# 2_power.net
KiCad netlist of a schematic drawn in Altium Designer
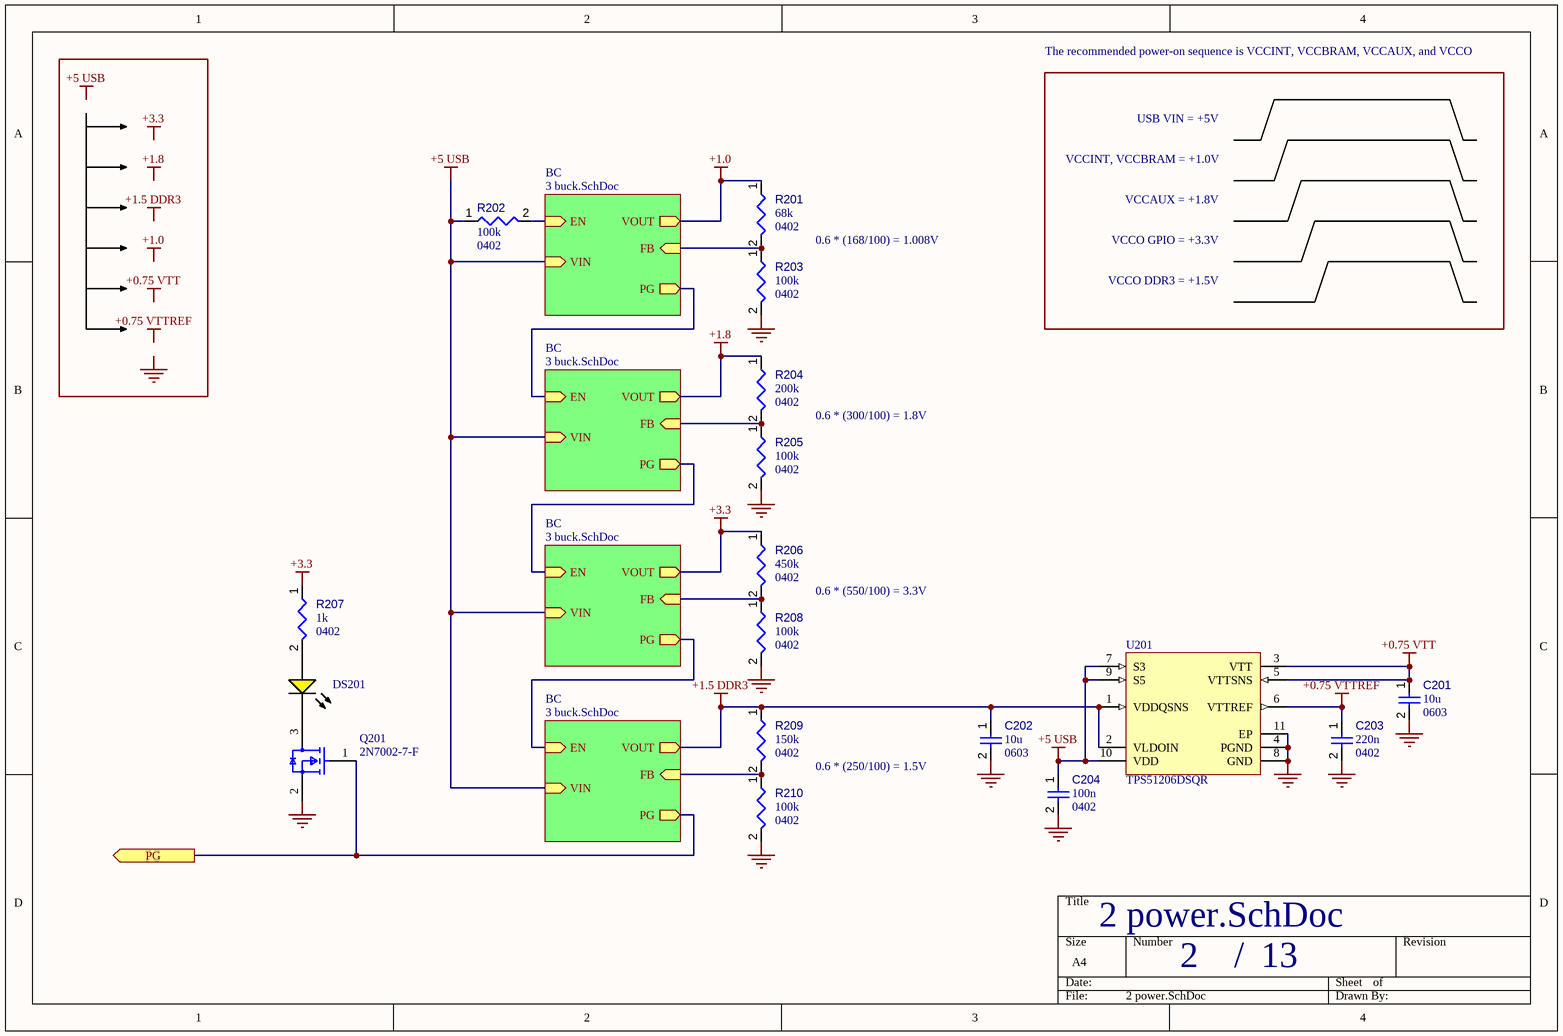
[diagram p0: 2 power.SchDoc]

(export (version "E")
  (design (tool "Eeschema 10.0.6"))
  (components
    (comp (ref "C201")
      (value "10u")
      (footprint "CAPC0603(1608)100_L")
      (description "Capacitor")
      (fields (field (name "CASE/PACKAGE") "0603") (field (name "Comment") "Capacitors,0603,10u"))
      (libsource (lib "UBC Uncrewed Aircraft Systems") (part "CAP-NP-2"))
    )
    (comp (ref "C202")
      (value "10u")
      (footprint "CAPC0603(1608)100_L")
      (description "Capacitor")
      (fields (field (name "CASE/PACKAGE") "0603") (field (name "Comment") "Capacitors,0603,10u"))
      (libsource (lib "UBC Uncrewed Aircraft Systems") (part "CAP-NP-2"))
    )
    (comp (ref "C203")
      (value "220n")
      (footprint "CAPC0402(1005)60_L")
      (description "Capacitor")
      (fields (field (name "CASE/PACKAGE") "0402") (field (name "Comment") "Capacitors,0402,220n,16"))
      (libsource (lib "UBC Uncrewed Aircraft Systems") (part "CAP-NP-2"))
    )
    (comp (ref "C204")
      (value "100n")
      (footprint "CAPC0402(1005)60_L")
      (description "Capacitor")
      (fields (field (name "CASE/PACKAGE") "0402") (field (name "Comment") "Capacitors,0402,100n,16"))
      (libsource (lib "UBC Uncrewed Aircraft Systems") (part "CAP-NP-2"))
    )
    (comp (ref "DS201")
      (value "SML-LX0603YW-TR")
      (footprint "LUMX-SML-LX0603_V")
      (fields (field (name "MANUFACTURER") "Lumex"))
      (libsource (lib "Altium Content Vault") (part "LED-YELLOW-AK-2"))
    )
    (comp (ref "Q201")
      (value "2N7002-7-F")
      (footprint "FP-SOT23-MFG")
      (description "MOSFET N-CH 60V 115MA SOT23-3")
      (fields (field (name "VOLTAGE") "60V"))
      (libsource (lib "Altium Content Vault") (part "3b9c635fedb024a5347a57b145af9cc"))
    )
    (comp (ref "R201")
      (value "68k")
      (footprint "RESC0402(1005)_L")
      (description "Resistor")
      (fields
        (field (name "CASE/PACKAGE") "0402")
        (field (name "TOLERANCE") "1%")
        (field (name "Comment") "Resistors,0402,1%,68k")
      )
      (libsource (lib "UBC Uncrewed Aircraft Systems") (part "RES-2"))
    )
    (comp (ref "R202")
      (value "100k")
      (footprint "RESC0402(1005)_L")
      (description "Resistor")
      (fields
        (field (name "CASE/PACKAGE") "0402")
        (field (name "TOLERANCE") "1%")
        (field (name "Comment") "Resistors,0402,1%,100k")
      )
      (libsource (lib "UBC Uncrewed Aircraft Systems") (part "RES-2"))
    )
    (comp (ref "R203")
      (value "100k")
      (footprint "RESC0402(1005)_L")
      (description "Resistor")
      (fields
        (field (name "CASE/PACKAGE") "0402")
        (field (name "TOLERANCE") "1%")
        (field (name "Comment") "Resistors,0402,1%,100k")
      )
      (libsource (lib "UBC Uncrewed Aircraft Systems") (part "RES-2"))
    )
    (comp (ref "R204")
      (value "200k")
      (footprint "RESC0402(1005)_L")
      (description "Resistor")
      (fields
        (field (name "CASE/PACKAGE") "0402")
        (field (name "TOLERANCE") "1%")
        (field (name "Comment") "Resistors,0402,1%,200k")
      )
      (libsource (lib "UBC Uncrewed Aircraft Systems") (part "RES-2"))
    )
    (comp (ref "R205")
      (value "100k")
      (footprint "RESC0402(1005)_L")
      (description "Resistor")
      (fields
        (field (name "CASE/PACKAGE") "0402")
        (field (name "TOLERANCE") "1%")
        (field (name "Comment") "Resistors,0402,1%,100k")
      )
      (libsource (lib "UBC Uncrewed Aircraft Systems") (part "RES-2"))
    )
    (comp (ref "R206")
      (value "450k")
      (footprint "RESC0402(1005)_L")
      (description "Resistor")
      (fields
        (field (name "CASE/PACKAGE") "0402")
        (field (name "TOLERANCE") "1%")
        (field (name "Comment") "Resistors,0402,1%,450k")
      )
      (libsource (lib "UBC Uncrewed Aircraft Systems") (part "RES-2"))
    )
    (comp (ref "R207")
      (value "1k")
      (footprint "RESC0402(1005)_L")
      (description "Resistor")
      (fields (field (name "CASE/PACKAGE") "0402") (field (name "Comment") "Resistors,0402,1k"))
      (libsource (lib "UBC Uncrewed Aircraft Systems") (part "RES-2"))
    )
    (comp (ref "R208")
      (value "100k")
      (footprint "RESC0402(1005)_L")
      (description "Resistor")
      (fields
        (field (name "CASE/PACKAGE") "0402")
        (field (name "TOLERANCE") "1%")
        (field (name "Comment") "Resistors,0402,1%,100k")
      )
      (libsource (lib "UBC Uncrewed Aircraft Systems") (part "RES-2"))
    )
    (comp (ref "R209")
      (value "150k")
      (footprint "RESC0402(1005)_L")
      (description "Resistor")
      (fields
        (field (name "CASE/PACKAGE") "0402")
        (field (name "TOLERANCE") "1%")
        (field (name "Comment") "Resistors,0402,1%,150k")
      )
      (libsource (lib "UBC Uncrewed Aircraft Systems") (part "RES-2"))
    )
    (comp (ref "R210")
      (value "100k")
      (footprint "RESC0402(1005)_L")
      (description "Resistor")
      (fields
        (field (name "CASE/PACKAGE") "0402")
        (field (name "TOLERANCE") "1%")
        (field (name "Comment") "Resistors,0402,1%,100k")
      )
      (libsource (lib "UBC Uncrewed Aircraft Systems") (part "RES-2"))
    )
    (comp (ref "U201")
      (value "TPS51206DSQR")
      (footprint "DSQ0010A_V")
      (fields (field (name "MANUFACTURER") "Texas Instruments"))
      (libsource (lib "Altium Content Vault") (part "TI-TPS51206DSQ10-1500X900TP"))
    )
  )
  (nets
    (net (code "1") (name "+0.75 VTT") (class "Default")
      (node (ref "C201") (pin "1") (pinfunction "1_1") (pintype "passive"))
      (node (ref "U201") (pin "3") (pinfunction "VTT_3") (pintype "power_in"))
      (node (ref "U201") (pin "5") (pinfunction "VTTSNS_5") (pintype "input"))
    )
    (net (code "2") (name "+0.75 VTTREF") (class "Default")
      (node (ref "C203") (pin "1") (pinfunction "1_1") (pintype "passive"))
      (node (ref "U201") (pin "6") (pinfunction "VTTREF_6") (pintype "output"))
    )
    (net (code "3") (name "+1.0") (class "Default")
      (node (ref "R201") (pin "1") (pinfunction "1_1") (pintype "passive"))
    )
    (net (code "4") (name "+1.5 DDR3") (class "Default")
      (node (ref "C202") (pin "1") (pinfunction "1_1") (pintype "passive"))
      (node (ref "R209") (pin "1") (pinfunction "1_1") (pintype "passive"))
      (node (ref "U201") (pin "1") (pinfunction "VDDQSNS_1") (pintype "input"))
      (node (ref "U201") (pin "2") (pinfunction "VLDOIN_2") (pintype "power_in"))
    )
    (net (code "5") (name "+1.8") (class "Default")
      (node (ref "R204") (pin "1") (pinfunction "1_1") (pintype "passive"))
    )
    (net (code "6") (name "+3.3") (class "Default")
      (node (ref "R206") (pin "1") (pinfunction "1_1") (pintype "passive"))
      (node (ref "R207") (pin "1") (pinfunction "1_1") (pintype "passive"))
    )
    (net (code "7") (name "+5 USB") (class "Default")
      (node (ref "C204") (pin "1") (pinfunction "1_1") (pintype "passive"))
      (node (ref "R202") (pin "1") (pinfunction "1_1") (pintype "passive"))
      (node (ref "U201") (pin "10") (pinfunction "VDD_10") (pintype "power_in"))
      (node (ref "U201") (pin "7") (pinfunction "S3_7") (pintype "input"))
      (node (ref "U201") (pin "9") (pinfunction "S5_9") (pintype "input"))
    )
    (net (code "8") (name "/EN") (class "Default")
      (node (ref "R202") (pin "2") (pinfunction "2_2") (pintype "passive"))
    )
    (net (code "9") (name "/FB") (class "Default")
      (node (ref "R206") (pin "2") (pinfunction "2_2") (pintype "passive"))
      (node (ref "R208") (pin "1") (pinfunction "1_1") (pintype "passive"))
    )
    (net (code "10") (name "/FB_1") (class "Default")
      (node (ref "R201") (pin "2") (pinfunction "2_2") (pintype "passive"))
      (node (ref "R203") (pin "1") (pinfunction "1_1") (pintype "passive"))
    )
    (net (code "11") (name "/FB_2") (class "Default")
      (node (ref "R204") (pin "2") (pinfunction "2_2") (pintype "passive"))
      (node (ref "R205") (pin "1") (pinfunction "1_1") (pintype "passive"))
    )
    (net (code "12") (name "/FB_3") (class "Default")
      (node (ref "R209") (pin "2") (pinfunction "2_2") (pintype "passive"))
      (node (ref "R210") (pin "1") (pinfunction "1_1") (pintype "passive"))
    )
    (net (code "13") (name "/PG") (class "Default")
      (node (ref "Q201") (pin "1") (pinfunction "G_1") (pintype "passive"))
    )
    (net (code "17") (name "GND") (class "Default")
      (node (ref "C201") (pin "2") (pinfunction "2_2") (pintype "passive"))
      (node (ref "C202") (pin "2") (pinfunction "2_2") (pintype "passive"))
      (node (ref "C203") (pin "2") (pinfunction "2_2") (pintype "passive"))
      (node (ref "C204") (pin "2") (pinfunction "2_2") (pintype "passive"))
      (node (ref "Q201") (pin "2") (pinfunction "S_2") (pintype "passive"))
      (node (ref "R203") (pin "2") (pinfunction "2_2") (pintype "passive"))
      (node (ref "R205") (pin "2") (pinfunction "2_2") (pintype "passive"))
      (node (ref "R208") (pin "2") (pinfunction "2_2") (pintype "passive"))
      (node (ref "R210") (pin "2") (pinfunction "2_2") (pintype "passive"))
      (node (ref "U201") (pin "11") (pinfunction "EP_11") (pintype "power_in"))
      (node (ref "U201") (pin "4") (pinfunction "PGND_4") (pintype "power_in"))
      (node (ref "U201") (pin "8") (pinfunction "GND_8") (pintype "power_in"))
    )
    (net (code "18") (name "Net-(DS201-A)") (class "Default")
      (node (ref "DS201") (pin "1") (pinfunction "A_1") (pintype "passive"))
      (node (ref "R207") (pin "2") (pinfunction "2_2") (pintype "passive"))
    )
    (net (code "19") (name "Net-(DS201-K)") (class "Default")
      (node (ref "DS201") (pin "2") (pinfunction "K_2") (pintype "passive"))
      (node (ref "Q201") (pin "3") (pinfunction "D_3") (pintype "passive"))
    )
  )
)
